# 8805.net
KiCad netlist of a schematic drawn in Altium Designer
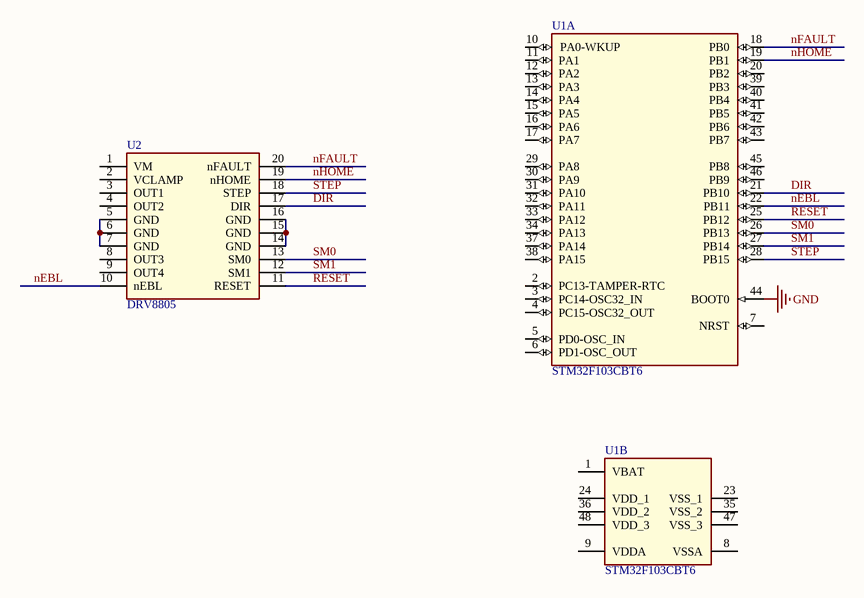
[diagram p0: 8805.SchDoc]

(export (version "E")
  (design (tool "Eeschema 10.0.6"))
  (components
    (comp (ref "U1")
      (value "STM32F103CBT6")
      (footprint "STM-LQFP48_N")
      (libsource (lib "8805") (part "STM32F103CBT6"))
    )
    (comp (ref "U2") (value "DRV8805") (libsource (lib "8805") (part "DRV8805")))
  )
  (nets
    (net (code "1") (name "/DIR") (class "Default")
      (node (ref "U1") (pin "21") (pinfunction "PB10_21") (pintype "bidirectional"))
      (node (ref "U2") (pin "17") (pinfunction "DIR_17") (pintype "passive"))
    )
    (net (code "2") (name "/RESET") (class "Default")
      (node (ref "U1") (pin "25") (pinfunction "PB12_25") (pintype "bidirectional"))
      (node (ref "U2") (pin "11") (pinfunction "RESET_11") (pintype "passive"))
    )
    (net (code "3") (name "/SM0") (class "Default")
      (node (ref "U1") (pin "26") (pinfunction "PB13_26") (pintype "bidirectional"))
      (node (ref "U2") (pin "13") (pinfunction "SM0_13") (pintype "passive"))
    )
    (net (code "4") (name "/SM1") (class "Default")
      (node (ref "U1") (pin "27") (pinfunction "PB14_27") (pintype "bidirectional"))
      (node (ref "U2") (pin "12") (pinfunction "SM1_12") (pintype "passive"))
    )
    (net (code "5") (name "/STEP") (class "Default")
      (node (ref "U1") (pin "28") (pinfunction "PB15_28") (pintype "bidirectional"))
      (node (ref "U2") (pin "18") (pinfunction "STEP_18") (pintype "passive"))
    )
    (net (code "6") (name "/nEBL") (class "Default")
      (node (ref "U1") (pin "22") (pinfunction "PB11_22") (pintype "bidirectional"))
      (node (ref "U2") (pin "10") (pinfunction "nEBL_10") (pintype "passive"))
    )
    (net (code "7") (name "/nFAULT") (class "Default")
      (node (ref "U1") (pin "18") (pinfunction "PB0_18") (pintype "bidirectional"))
      (node (ref "U2") (pin "20") (pinfunction "nFAULT_20") (pintype "passive"))
    )
    (net (code "8") (name "/nHOME") (class "Default")
      (node (ref "U1") (pin "19") (pinfunction "PB1_19") (pintype "bidirectional"))
      (node (ref "U2") (pin "19") (pinfunction "nHOME_19") (pintype "passive"))
    )
    (net (code "9") (name "GND") (class "Default")
      (node (ref "U1") (pin "44") (pinfunction "BOOT0_44") (pintype "input"))
    )
    (net (code "10") (name "Net-(U2-GND-Pad5)") (class "Default")
      (node (ref "U2") (pin "5") (pinfunction "GND_5") (pintype "passive"))
      (node (ref "U2") (pin "6") (pinfunction "GND_6") (pintype "passive"))
      (node (ref "U2") (pin "7") (pinfunction "GND_7") (pintype "passive"))
    )
    (net (code "11") (name "Net-(U2-GND-Pad14)") (class "Default")
      (node (ref "U2") (pin "14") (pinfunction "GND_14") (pintype "passive"))
      (node (ref "U2") (pin "15") (pinfunction "GND_15") (pintype "passive"))
      (node (ref "U2") (pin "16") (pinfunction "GND_16") (pintype "passive"))
    )
    (net (code "12") (name "unconnected-(U1A-NRST-Pad7)") (class "Default")
      (node (ref "U1") (pin "7") (pinfunction "NRST_7") (pintype "bidirectional"))
    )
    (net (code "13") (name "unconnected-(U1A-PA0-WKUP-Pad10)") (class "Default")
      (node (ref "U1") (pin "10") (pinfunction "PA0-WKUP_10") (pintype "bidirectional"))
    )
    (net (code "14") (name "unconnected-(U1A-PA1-Pad11)") (class "Default")
      (node (ref "U1") (pin "11") (pinfunction "PA1_11") (pintype "bidirectional"))
    )
    (net (code "15") (name "unconnected-(U1A-PA2-Pad12)") (class "Default")
      (node (ref "U1") (pin "12") (pinfunction "PA2_12") (pintype "bidirectional"))
    )
    (net (code "16") (name "unconnected-(U1A-PA3-Pad13)") (class "Default")
      (node (ref "U1") (pin "13") (pinfunction "PA3_13") (pintype "bidirectional"))
    )
    (net (code "17") (name "unconnected-(U1A-PA4-Pad14)") (class "Default")
      (node (ref "U1") (pin "14") (pinfunction "PA4_14") (pintype "bidirectional"))
    )
    (net (code "18") (name "unconnected-(U1A-PA5-Pad15)") (class "Default")
      (node (ref "U1") (pin "15") (pinfunction "PA5_15") (pintype "bidirectional"))
    )
    (net (code "19") (name "unconnected-(U1A-PA6-Pad16)") (class "Default")
      (node (ref "U1") (pin "16") (pinfunction "PA6_16") (pintype "bidirectional"))
    )
    (net (code "20") (name "unconnected-(U1A-PA7-Pad17)") (class "Default")
      (node (ref "U1") (pin "17") (pinfunction "PA7_17") (pintype "bidirectional"))
    )
    (net (code "21") (name "unconnected-(U1A-PA8-Pad29)") (class "Default")
      (node (ref "U1") (pin "29") (pinfunction "PA8_29") (pintype "bidirectional"))
    )
    (net (code "22") (name "unconnected-(U1A-PA9-Pad30)") (class "Default")
      (node (ref "U1") (pin "30") (pinfunction "PA9_30") (pintype "bidirectional"))
    )
    (net (code "23") (name "unconnected-(U1A-PA10-Pad31)") (class "Default")
      (node (ref "U1") (pin "31") (pinfunction "PA10_31") (pintype "bidirectional"))
    )
    (net (code "24") (name "unconnected-(U1A-PA11-Pad32)") (class "Default")
      (node (ref "U1") (pin "32") (pinfunction "PA11_32") (pintype "bidirectional"))
    )
    (net (code "25") (name "unconnected-(U1A-PA12-Pad33)") (class "Default")
      (node (ref "U1") (pin "33") (pinfunction "PA12_33") (pintype "bidirectional"))
    )
    (net (code "26") (name "unconnected-(U1A-PA13-Pad34)") (class "Default")
      (node (ref "U1") (pin "34") (pinfunction "PA13_34") (pintype "bidirectional"))
    )
    (net (code "27") (name "unconnected-(U1A-PA14-Pad37)") (class "Default")
      (node (ref "U1") (pin "37") (pinfunction "PA14_37") (pintype "bidirectional"))
    )
    (net (code "28") (name "unconnected-(U1A-PA15-Pad38)") (class "Default")
      (node (ref "U1") (pin "38") (pinfunction "PA15_38") (pintype "bidirectional"))
    )
    (net (code "29") (name "unconnected-(U1A-PB2-Pad20)") (class "Default")
      (node (ref "U1") (pin "20") (pinfunction "PB2_20") (pintype "bidirectional"))
    )
    (net (code "30") (name "unconnected-(U1A-PB3-Pad39)") (class "Default")
      (node (ref "U1") (pin "39") (pinfunction "PB3_39") (pintype "bidirectional"))
    )
    (net (code "31") (name "unconnected-(U1A-PB4-Pad40)") (class "Default")
      (node (ref "U1") (pin "40") (pinfunction "PB4_40") (pintype "bidirectional"))
    )
    (net (code "32") (name "unconnected-(U1A-PB5-Pad41)") (class "Default")
      (node (ref "U1") (pin "41") (pinfunction "PB5_41") (pintype "bidirectional"))
    )
    (net (code "33") (name "unconnected-(U1A-PB6-Pad42)") (class "Default")
      (node (ref "U1") (pin "42") (pinfunction "PB6_42") (pintype "bidirectional"))
    )
    (net (code "34") (name "unconnected-(U1A-PB7-Pad43)") (class "Default")
      (node (ref "U1") (pin "43") (pinfunction "PB7_43") (pintype "bidirectional"))
    )
    (net (code "35") (name "unconnected-(U1A-PB8-Pad45)") (class "Default")
      (node (ref "U1") (pin "45") (pinfunction "PB8_45") (pintype "bidirectional"))
    )
    (net (code "36") (name "unconnected-(U1A-PB9-Pad46)") (class "Default")
      (node (ref "U1") (pin "46") (pinfunction "PB9_46") (pintype "bidirectional"))
    )
    (net (code "37") (name "unconnected-(U1A-PC13-TAMPER-RTC-Pad2)") (class "Default")
      (node (ref "U1") (pin "2") (pinfunction "PC13-TAMPER-RTC_2") (pintype "bidirectional"))
    )
    (net (code "38") (name "unconnected-(U1A-PC14-OSC32_IN-Pad3)") (class "Default")
      (node (ref "U1") (pin "3") (pinfunction "PC14-OSC32_IN_3") (pintype "bidirectional"))
    )
    (net (code "39") (name "unconnected-(U1A-PC15-OSC32_OUT-Pad4)") (class "Default")
      (node (ref "U1") (pin "4") (pinfunction "PC15-OSC32_OUT_4") (pintype "bidirectional"))
    )
    (net (code "40") (name "unconnected-(U1A-PD0-OSC_IN-Pad5)") (class "Default")
      (node (ref "U1") (pin "5") (pinfunction "PD0-OSC_IN_5") (pintype "bidirectional"))
    )
    (net (code "41") (name "unconnected-(U1A-PD1-OSC_OUT-Pad6)") (class "Default")
      (node (ref "U1") (pin "6") (pinfunction "PD1-OSC_OUT_6") (pintype "bidirectional"))
    )
    (net (code "42") (name "unconnected-(U1B-VBAT-Pad1)") (class "Default")
      (node (ref "U1") (pin "1") (pinfunction "VBAT_1") (pintype "power_in"))
    )
    (net (code "43") (name "unconnected-(U1B-VDDA-Pad9)") (class "Default")
      (node (ref "U1") (pin "9") (pinfunction "VDDA_9") (pintype "power_in"))
    )
    (net (code "44") (name "unconnected-(U1B-VDD_1-Pad24)") (class "Default")
      (node (ref "U1") (pin "24") (pinfunction "VDD_1_24") (pintype "power_in"))
    )
    (net (code "45") (name "unconnected-(U1B-VDD_2-Pad36)") (class "Default")
      (node (ref "U1") (pin "36") (pinfunction "VDD_2_36") (pintype "power_in"))
    )
    (net (code "46") (name "unconnected-(U1B-VDD_3-Pad48)") (class "Default")
      (node (ref "U1") (pin "48") (pinfunction "VDD_3_48") (pintype "power_in"))
    )
    (net (code "47") (name "unconnected-(U1B-VSSA-Pad8)") (class "Default")
      (node (ref "U1") (pin "8") (pinfunction "VSSA_8") (pintype "power_in"))
    )
    (net (code "48") (name "unconnected-(U1B-VSS_1-Pad23)") (class "Default")
      (node (ref "U1") (pin "23") (pinfunction "VSS_1_23") (pintype "power_in"))
    )
    (net (code "49") (name "unconnected-(U1B-VSS_2-Pad35)") (class "Default")
      (node (ref "U1") (pin "35") (pinfunction "VSS_2_35") (pintype "power_in"))
    )
    (net (code "50") (name "unconnected-(U1B-VSS_3-Pad47)") (class "Default")
      (node (ref "U1") (pin "47") (pinfunction "VSS_3_47") (pintype "power_in"))
    )
    (net (code "51") (name "unconnected-(U2-OUT1-Pad3)") (class "Default")
      (node (ref "U2") (pin "3") (pinfunction "OUT1_3") (pintype "passive"))
    )
    (net (code "52") (name "unconnected-(U2-OUT2-Pad4)") (class "Default")
      (node (ref "U2") (pin "4") (pinfunction "OUT2_4") (pintype "passive"))
    )
    (net (code "53") (name "unconnected-(U2-OUT3-Pad8)") (class "Default")
      (node (ref "U2") (pin "8") (pinfunction "OUT3_8") (pintype "passive"))
    )
    (net (code "54") (name "unconnected-(U2-OUT4-Pad9)") (class "Default")
      (node (ref "U2") (pin "9") (pinfunction "OUT4_9") (pintype "passive"))
    )
    (net (code "55") (name "unconnected-(U2-VCLAMP-Pad2)") (class "Default")
      (node (ref "U2") (pin "2") (pinfunction "VCLAMP_2") (pintype "passive"))
    )
    (net (code "56") (name "unconnected-(U2-VM-Pad1)") (class "Default")
      (node (ref "U2") (pin "1") (pinfunction "VM_1") (pintype "passive"))
    )
  )
)
